# Sheet1.net
KiCad netlist of a schematic drawn in Altium Designer
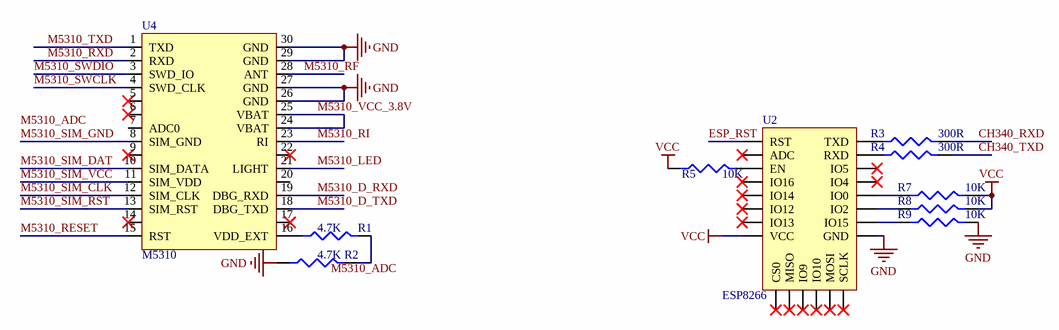
[diagram p0: Sheet1.SchDoc]

(export (version "E")
  (design (tool "Eeschema 10.0.6"))
  (components
    (comp (ref "R1") (value "4.7K") (libsource (lib "电阻电容电感") (part "电位器2")))
    (comp (ref "R2") (value "4.7K") (libsource (lib "电阻电容电感") (part "电位器2")))
    (comp (ref "R3") (value "300R") (libsource (lib "电阻电容电感") (part "电位器2")))
    (comp (ref "R4") (value "300R") (libsource (lib "电阻电容电感") (part "电位器2")))
    (comp (ref "R5") (value "10K") (libsource (lib "电阻电容电感") (part "电位器2")))
    (comp (ref "R7") (value "10K") (libsource (lib "电阻电容电感") (part "电位器2")))
    (comp (ref "R8") (value "10K") (libsource (lib "电阻电容电感") (part "电位器2")))
    (comp (ref "R9") (value "10K") (libsource (lib "电阻电容电感") (part "电位器2")))
    (comp (ref "U2") (value "ESP8266") (libsource (lib "Schlib1") (part "ESP8266")))
    (comp (ref "U4") (value "M5310") (libsource (lib "Schlib1") (part "NB")))
  )
  (nets
    (net (code "1") (name "/CH340_RXD") (class "Default")
      (node (ref "R3") (pin "2") (pinfunction "2_2") (pintype "passive"))
    )
    (net (code "2") (name "/CH340_TXD") (class "Default")
      (node (ref "R4") (pin "2") (pinfunction "2_2") (pintype "passive"))
    )
    (net (code "3") (name "/ESP_RST") (class "Default")
      (node (ref "U2") (pin "34") (pinfunction "RST_34") (pintype "passive"))
    )
    (net (code "5") (name "/M5310_D_RXD") (class "Default")
      (node (ref "U4") (pin "19") (pinfunction "DBG_RXD_19") (pintype "passive"))
    )
    (net (code "6") (name "/M5310_D_TXD") (class "Default")
      (node (ref "U4") (pin "18") (pinfunction "DBG_TXD_18") (pintype "passive"))
    )
    (net (code "7") (name "/M5310_LED") (class "Default")
      (node (ref "U4") (pin "21") (pinfunction "LIGHT_21") (pintype "passive"))
    )
    (net (code "8") (name "/M5310_RESET") (class "Default")
      (node (ref "U4") (pin "15") (pinfunction "RST_15") (pintype "passive"))
    )
    (net (code "9") (name "/M5310_RF") (class "Default")
      (node (ref "U4") (pin "28") (pinfunction "ANT_28") (pintype "passive"))
    )
    (net (code "10") (name "/M5310_RI") (class "Default")
      (node (ref "U4") (pin "23") (pinfunction "RI_23") (pintype "passive"))
    )
    (net (code "11") (name "/M5310_RXD") (class "Default")
      (node (ref "U4") (pin "2") (pinfunction "RXD_2") (pintype "passive"))
    )
    (net (code "12") (name "/M5310_SIM_CLK") (class "Default")
      (node (ref "U4") (pin "12") (pinfunction "SIM_CLK_12") (pintype "passive"))
    )
    (net (code "13") (name "/M5310_SIM_DAT") (class "Default")
      (node (ref "U4") (pin "10") (pinfunction "SIM_DATA_10") (pintype "passive"))
    )
    (net (code "14") (name "/M5310_SIM_GND") (class "Default")
      (node (ref "U4") (pin "8") (pinfunction "SIM_GND_8") (pintype "passive"))
    )
    (net (code "15") (name "/M5310_SIM_RST") (class "Default")
      (node (ref "U4") (pin "13") (pinfunction "SIM_RST_13") (pintype "passive"))
    )
    (net (code "16") (name "/M5310_SIM_VCC") (class "Default")
      (node (ref "U4") (pin "11") (pinfunction "SIM_VDD_11") (pintype "passive"))
    )
    (net (code "17") (name "/M5310_SWCLK") (class "Default")
      (node (ref "U4") (pin "4") (pinfunction "SWD_CLK_4") (pintype "passive"))
    )
    (net (code "18") (name "/M5310_SWDIO") (class "Default")
      (node (ref "U4") (pin "3") (pinfunction "SWD_IO_3") (pintype "passive"))
    )
    (net (code "19") (name "/M5310_TXD") (class "Default")
      (node (ref "U4") (pin "1") (pinfunction "TXD_1") (pintype "passive"))
    )
    (net (code "20") (name "/M5310_VCC_3.8V") (class "Default")
      (node (ref "U4") (pin "24") (pinfunction "VBAT_24") (pintype "passive"))
      (node (ref "U4") (pin "25") (pinfunction "VBAT_25") (pintype "passive"))
    )
    (net (code "21") (name "GND") (class "Default")
      (node (ref "R2") (pin "1") (pinfunction "1_1") (pintype "passive"))
      (node (ref "R9") (pin "2") (pinfunction "2_2") (pintype "passive"))
      (node (ref "U2") (pin "55") (pinfunction "GND_55") (pintype "passive"))
      (node (ref "U4") (pin "26") (pinfunction "GND_26") (pintype "passive"))
      (node (ref "U4") (pin "27") (pinfunction "GND_27") (pintype "passive"))
      (node (ref "U4") (pin "29") (pinfunction "GND_29") (pintype "passive"))
      (node (ref "U4") (pin "30") (pinfunction "GND_30") (pintype "passive"))
    )
    (net (code "22") (name "Net-(R1-Pad2)") (class "Default")
      (node (ref "R1") (pin "2") (pinfunction "2_2") (pintype "passive"))
      (node (ref "R2") (pin "2") (pinfunction "2_2") (pintype "passive"))
    )
    (net (code "23") (name "Net-(U2-IO0)") (class "Default")
      (node (ref "R7") (pin "1") (pinfunction "1_1") (pintype "passive"))
      (node (ref "U2") (pin "52") (pinfunction "IO0_52") (pintype "passive"))
    )
    (net (code "24") (name "Net-(U2-IO2)") (class "Default")
      (node (ref "R8") (pin "1") (pinfunction "1_1") (pintype "passive"))
      (node (ref "U2") (pin "53") (pinfunction "IO2_53") (pintype "passive"))
    )
    (net (code "25") (name "Net-(U2-IO15)") (class "Default")
      (node (ref "R9") (pin "1") (pinfunction "1_1") (pintype "passive"))
      (node (ref "U2") (pin "54") (pinfunction "IO15_54") (pintype "passive"))
    )
    (net (code "26") (name "Net-(U4-VDD_EXT)") (class "Default")
      (node (ref "R1") (pin "1") (pinfunction "1_1") (pintype "passive"))
      (node (ref "U4") (pin "16") (pinfunction "VDD_EXT_16") (pintype "passive"))
    )
    (net (code "27") (name "VCC") (class "Default")
      (node (ref "R5") (pin "1") (pinfunction "1_1") (pintype "passive"))
      (node (ref "R7") (pin "2") (pinfunction "2_2") (pintype "passive"))
      (node (ref "R8") (pin "2") (pinfunction "2_2") (pintype "passive"))
      (node (ref "U2") (pin "41") (pinfunction "VCC_41") (pintype "passive"))
    )
    (net (code "28") (name "unconnected-(R3-Pad1)") (class "Default")
      (node (ref "R3") (pin "1") (pinfunction "1_1") (pintype "passive"))
    )
    (net (code "29") (name "unconnected-(R4-Pad1)") (class "Default")
      (node (ref "R4") (pin "1") (pinfunction "1_1") (pintype "passive"))
    )
    (net (code "30") (name "unconnected-(R5-Pad2)") (class "Default")
      (node (ref "R5") (pin "2") (pinfunction "2_2") (pintype "passive"))
    )
    (net (code "31") (name "unconnected-(U2-ADC-Pad35)") (class "Default")
      (node (ref "U2") (pin "35") (pinfunction "ADC_35") (pintype "passive+no_connect"))
    )
    (net (code "32") (name "unconnected-(U2-CS0-Pad42)") (class "Default")
      (node (ref "U2") (pin "42") (pinfunction "CS0_42") (pintype "passive+no_connect"))
    )
    (net (code "33") (name "unconnected-(U2-EN-Pad36)") (class "Default")
      (node (ref "U2") (pin "36") (pinfunction "EN_36") (pintype "passive"))
    )
    (net (code "34") (name "unconnected-(U2-IO4-Pad51)") (class "Default")
      (node (ref "U2") (pin "51") (pinfunction "IO4_51") (pintype "passive+no_connect"))
    )
    (net (code "35") (name "unconnected-(U2-IO5-Pad50)") (class "Default")
      (node (ref "U2") (pin "50") (pinfunction "IO5_50") (pintype "passive+no_connect"))
    )
    (net (code "36") (name "unconnected-(U2-IO9-Pad44)") (class "Default")
      (node (ref "U2") (pin "44") (pinfunction "IO9_44") (pintype "passive+no_connect"))
    )
    (net (code "37") (name "unconnected-(U2-IO10-Pad45)") (class "Default")
      (node (ref "U2") (pin "45") (pinfunction "IO10_45") (pintype "passive+no_connect"))
    )
    (net (code "38") (name "unconnected-(U2-IO12-Pad39)") (class "Default")
      (node (ref "U2") (pin "39") (pinfunction "IO12_39") (pintype "passive+no_connect"))
    )
    (net (code "39") (name "unconnected-(U2-IO13-Pad40)") (class "Default")
      (node (ref "U2") (pin "40") (pinfunction "IO13_40") (pintype "passive+no_connect"))
    )
    (net (code "40") (name "unconnected-(U2-IO14-Pad38)") (class "Default")
      (node (ref "U2") (pin "38") (pinfunction "IO14_38") (pintype "passive+no_connect"))
    )
    (net (code "41") (name "unconnected-(U2-IO16-Pad37)") (class "Default")
      (node (ref "U2") (pin "37") (pinfunction "IO16_37") (pintype "passive+no_connect"))
    )
    (net (code "42") (name "unconnected-(U2-MISO-Pad43)") (class "Default")
      (node (ref "U2") (pin "43") (pinfunction "MISO_43") (pintype "passive+no_connect"))
    )
    (net (code "43") (name "unconnected-(U2-MOSI-Pad46)") (class "Default")
      (node (ref "U2") (pin "46") (pinfunction "MOSI_46") (pintype "passive+no_connect"))
    )
    (net (code "44") (name "unconnected-(U2-RXD-Pad49)") (class "Default")
      (node (ref "U2") (pin "49") (pinfunction "RXD_49") (pintype "passive"))
    )
    (net (code "45") (name "unconnected-(U2-SCLK-Pad47)") (class "Default")
      (node (ref "U2") (pin "47") (pinfunction "SCLK_47") (pintype "passive+no_connect"))
    )
    (net (code "46") (name "unconnected-(U2-TXD-Pad48)") (class "Default")
      (node (ref "U2") (pin "48") (pinfunction "TXD_48") (pintype "passive"))
    )
    (net (code "47") (name "unconnected-(U4-41-Pad5)") (class "Default")
      (node (ref "U4") (pin "5") (pinfunction "41_5") (pintype "passive+no_connect"))
    )
    (net (code "48") (name "unconnected-(U4-42-Pad6)") (class "Default")
      (node (ref "U4") (pin "6") (pinfunction "42_6") (pintype "passive+no_connect"))
    )
    (net (code "49") (name "unconnected-(U4-45-Pad9)") (class "Default")
      (node (ref "U4") (pin "9") (pinfunction "45_9") (pintype "passive+no_connect"))
    )
    (net (code "50") (name "unconnected-(U4-ADC0-Pad7)") (class "Default")
      (node (ref "U4") (pin "7") (pinfunction "ADC0_7") (pintype "passive"))
    )
    (net (code "51") (name "unconnected-(U4-Pad14)") (class "Default")
      (node (ref "U4") (pin "14") (pintype "passive+no_connect"))
    )
    (net (code "52") (name "unconnected-(U4-Pad17)") (class "Default")
      (node (ref "U4") (pin "17") (pinfunction "17_17") (pintype "passive+no_connect"))
    )
    (net (code "53") (name "unconnected-(U4-Pad20)") (class "Default")
      (node (ref "U4") (pin "20") (pinfunction "20_20") (pintype "passive"))
    )
    (net (code "54") (name "unconnected-(U4-Pad22)") (class "Default")
      (node (ref "U4") (pin "22") (pinfunction "22_22") (pintype "passive+no_connect"))
    )
  )
)
